# lab6_2020-12-28_19-20-47.net
KiCad netlist of a schematic drawn in EasyEDA
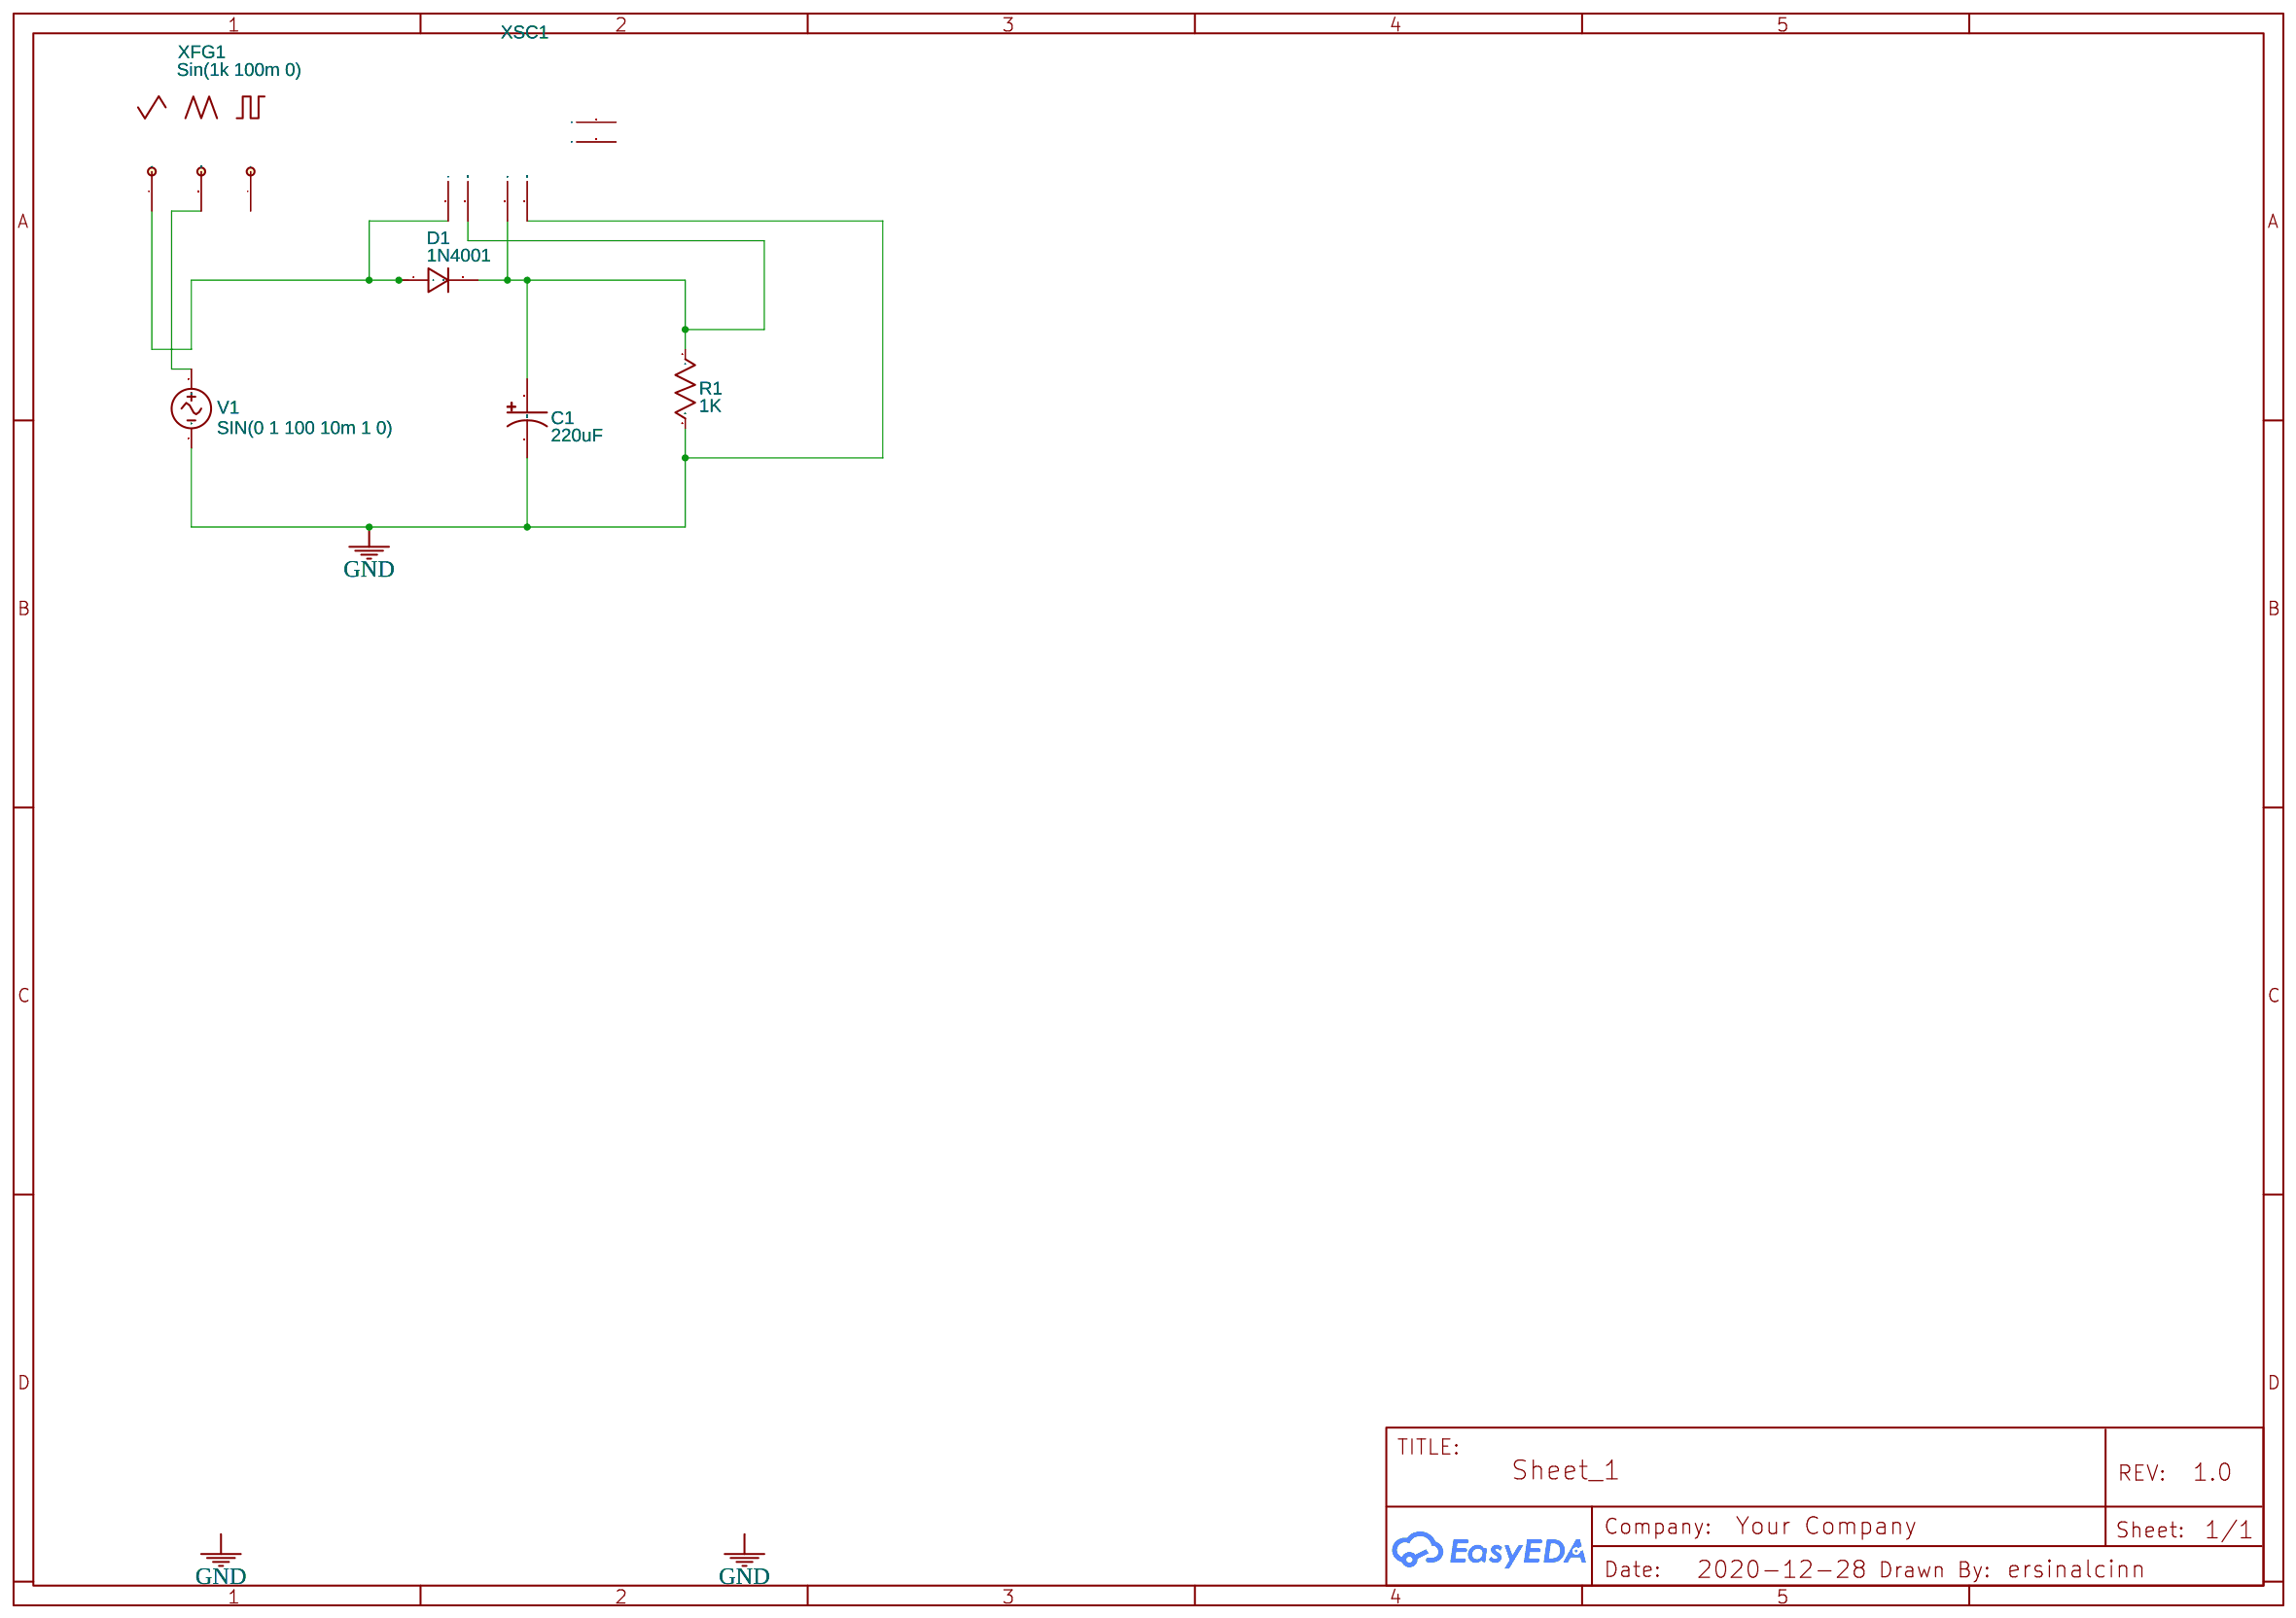
[diagram p0: schematic sheet]

(export (version "E")
  (design (tool "Eeschema 10.0.6"))
  (components
    (comp (ref "C1") (value "220uF") (libsource (lib "") (part "Capacitor_Electrolytic_US")))
    (comp (ref "D1") (value "1N4001") (libsource (lib "") (part "1N4148")))
    (comp (ref "R1") (value "1K") (libsource (lib "") (part "Resistor_US")))
    (comp (ref "V1") (value "SIN(0 1 100 10m 1 0)") (libsource (lib "") (part "VSin")))
    (comp (ref "XFG1") (value "Sin(1k 100m 0)") (libsource (lib "") (part "FUNCTIONGENERATOR")))
    (comp (ref "XSC1") (value "Oscilloscope") (libsource (lib "") (part "OSCILLOSCOPE")))
  )
  (nets
    (net (code "1") (name "GND") (class "Default")
      (node (ref "C1") (pin "2") (pinfunction "2_2") (pintype "unspecified"))
      (node (ref "R1") (pin "2") (pinfunction "2_2") (pintype "unspecified"))
      (node (ref "V1") (pin "2") (pinfunction "2_2") (pintype "unspecified"))
      (node (ref "XSC1") (pin "4") (pinfunction "GND2_4") (pintype "unspecified"))
    )
    (net (code "2") (name "Net-(D1-A)") (class "Default")
      (node (ref "D1") (pin "1") (pinfunction "A_1") (pintype "unspecified"))
      (node (ref "XFG1") (pin "+") (pinfunction "+_+") (pintype "unspecified"))
      (node (ref "XSC1") (pin "1") (pinfunction "A_1") (pintype "unspecified"))
    )
    (net (code "3") (name "Net-(D1-K)") (class "Default")
      (node (ref "C1") (pin "1") (pinfunction "1_1") (pintype "unspecified"))
      (node (ref "D1") (pin "2") (pinfunction "K_2") (pintype "unspecified"))
      (node (ref "R1") (pin "1") (pinfunction "1_1") (pintype "unspecified"))
      (node (ref "XSC1") (pin "2") (pinfunction "GND1_2") (pintype "unspecified"))
      (node (ref "XSC1") (pin "3") (pinfunction "B_3") (pintype "unspecified"))
    )
    (net (code "4") (name "Net-(V1-Pad1)") (class "Default")
      (node (ref "V1") (pin "1") (pinfunction "1_1") (pintype "unspecified"))
      (node (ref "XFG1") (pin "COM") (pinfunction "COM_COM") (pintype "unspecified"))
    )
    (net (code "5") (name "unconnected-(XFG1-Pad-)") (class "Default")
      (node (ref "XFG1") (pin "-") (pinfunction "-_-") (pintype "unspecified"))
    )
    (net (code "6") (name "unconnected-(XSC1-T+-Pad5)") (class "Default")
      (node (ref "XSC1") (pin "5") (pinfunction "T+_5") (pintype "unspecified"))
    )
    (net (code "7") (name "unconnected-(XSC1-T--Pad6)") (class "Default")
      (node (ref "XSC1") (pin "6") (pinfunction "T-_6") (pintype "unspecified"))
    )
  )
)
